# DecadeCounterViewer.net
KiCad netlist of a schematic drawn in EAGLE
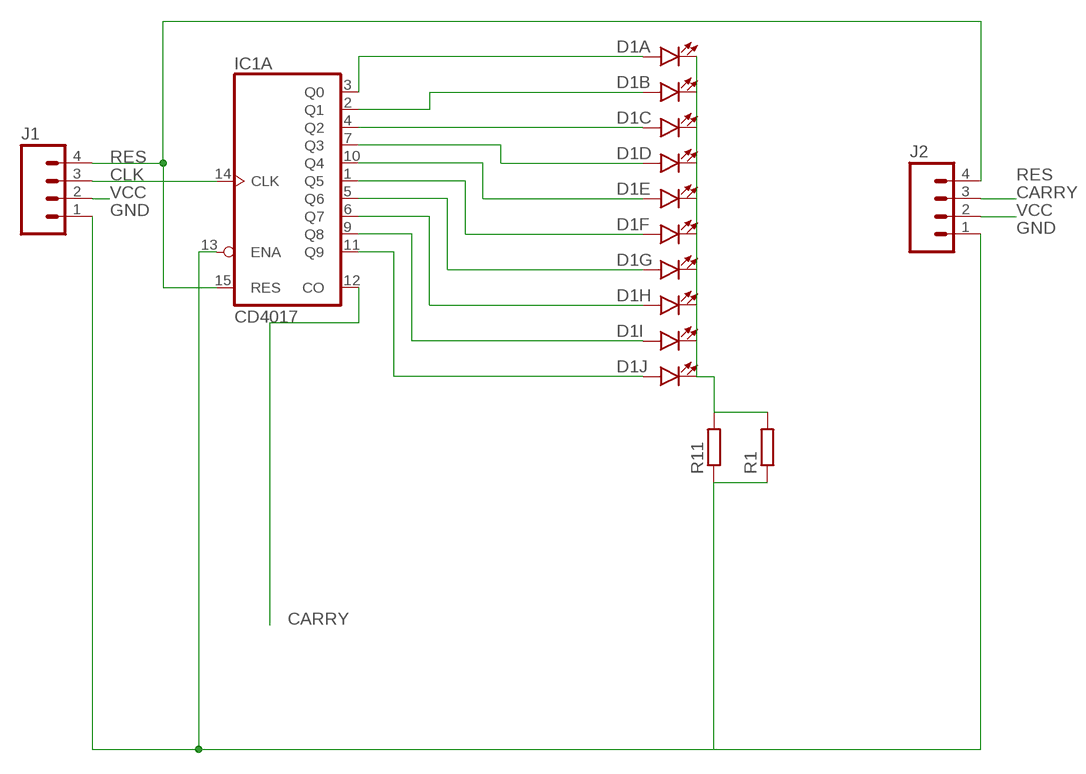
[diagram p0: schematic, sheet 1]

(export (version "E")
  (design (tool "Eeschema 10.0.6"))
  (components
    (comp (ref "D1")
      (value "LED_BARGRAPH_10")
      (footprint "eagle-import:LED_BARGAPH_10")
      (libsource (lib "eagle-import") (part "LED_BARGRAPH_10"))
    )
    (comp (ref "IC1")
      (value "CD4017")
      (footprint "eagle-import:DIL16")
      (libsource (lib "eagle-import") (part "CD4017"))
    )
    (comp (ref "J1")
      (value "M04LOCK")
      (footprint "eagle-import:1X04_LOCK")
      (libsource (lib "eagle-import") (part "M04LOCK"))
    )
    (comp (ref "J2")
      (value "M04LOCK")
      (footprint "eagle-import:1X04_LOCK")
      (libsource (lib "eagle-import") (part "M04LOCK"))
    )
    (comp (ref "R1")
      (value "R-EU_0204/7")
      (footprint "eagle-import:0204_7")
      (libsource (lib "eagle-import") (part "R-EU_0204/7"))
    )
    (comp (ref "R11")
      (value "R-EU_R1206")
      (footprint "eagle-import:R1206")
      (libsource (lib "eagle-import") (part "R-EU_R1206"))
    )
  )
  (nets
    (net (code "1") (name "/CARRY") (class "Default")
      (node (ref "IC1") (pin "12") (pinfunction "CO_12") (pintype "output"))
      (node (ref "J2") (pin "3") (pinfunction "3_3") (pintype "passive"))
    )
    (net (code "2") (name "/CLK") (class "Default")
      (node (ref "IC1") (pin "14") (pinfunction "CLK_14") (pintype "input"))
      (node (ref "J1") (pin "3") (pinfunction "3_3") (pintype "passive"))
    )
    (net (code "3") (name "/GND") (class "Default")
      (node (ref "IC1") (pin "13") (pinfunction "ENA_13") (pintype "input"))
      (node (ref "J1") (pin "1") (pinfunction "1_1") (pintype "passive"))
      (node (ref "J2") (pin "1") (pinfunction "1_1") (pintype "passive"))
      (node (ref "R1") (pin "1") (pinfunction "1_1") (pintype "passive"))
      (node (ref "R11") (pin "1") (pinfunction "1_1") (pintype "passive"))
    )
    (net (code "4") (name "/RES") (class "Default")
      (node (ref "IC1") (pin "15") (pinfunction "RES_15") (pintype "input"))
      (node (ref "J1") (pin "4") (pinfunction "4_4") (pintype "passive"))
      (node (ref "J2") (pin "4") (pinfunction "4_4") (pintype "passive"))
    )
    (net (code "5") (name "/VCC") (class "Default")
      (node (ref "J1") (pin "2") (pinfunction "2_2") (pintype "passive"))
      (node (ref "J2") (pin "2") (pinfunction "2_2") (pintype "passive"))
    )
    (net (code "6") (name "Net-(D1A-A)") (class "Default")
      (node (ref "D1") (pin "1") (pinfunction "A_1") (pintype "passive"))
      (node (ref "IC1") (pin "3") (pinfunction "Q0_3") (pintype "output"))
    )
    (net (code "7") (name "Net-(D1A-C)") (class "Default")
      (node (ref "D1") (pin "11") (pinfunction "C_11") (pintype "passive"))
      (node (ref "D1") (pin "12") (pinfunction "C_12") (pintype "passive"))
      (node (ref "D1") (pin "13") (pinfunction "C_13") (pintype "passive"))
      (node (ref "D1") (pin "14") (pinfunction "C_14") (pintype "passive"))
      (node (ref "D1") (pin "15") (pinfunction "C_15") (pintype "passive"))
      (node (ref "D1") (pin "16") (pinfunction "C_16") (pintype "passive"))
      (node (ref "D1") (pin "17") (pinfunction "C_17") (pintype "passive"))
      (node (ref "D1") (pin "18") (pinfunction "C_18") (pintype "passive"))
      (node (ref "D1") (pin "19") (pinfunction "C_19") (pintype "passive"))
      (node (ref "D1") (pin "20") (pinfunction "C_20") (pintype "passive"))
      (node (ref "R1") (pin "2") (pinfunction "2_2") (pintype "passive"))
      (node (ref "R11") (pin "2") (pinfunction "2_2") (pintype "passive"))
    )
    (net (code "8") (name "Net-(D1B-A)") (class "Default")
      (node (ref "D1") (pin "2") (pinfunction "A_2") (pintype "passive"))
      (node (ref "IC1") (pin "2") (pinfunction "Q1_2") (pintype "output"))
    )
    (net (code "9") (name "Net-(D1C-A)") (class "Default")
      (node (ref "D1") (pin "3") (pinfunction "A_3") (pintype "passive"))
      (node (ref "IC1") (pin "4") (pinfunction "Q2_4") (pintype "output"))
    )
    (net (code "10") (name "Net-(D1D-A)") (class "Default")
      (node (ref "D1") (pin "4") (pinfunction "A_4") (pintype "passive"))
      (node (ref "IC1") (pin "7") (pinfunction "Q3_7") (pintype "output"))
    )
    (net (code "11") (name "Net-(D1E-A)") (class "Default")
      (node (ref "D1") (pin "5") (pinfunction "A_5") (pintype "passive"))
      (node (ref "IC1") (pin "10") (pinfunction "Q4_10") (pintype "output"))
    )
    (net (code "12") (name "Net-(D1F-A)") (class "Default")
      (node (ref "D1") (pin "6") (pinfunction "A_6") (pintype "passive"))
      (node (ref "IC1") (pin "1") (pinfunction "Q5_1") (pintype "output"))
    )
    (net (code "13") (name "Net-(D1G-A)") (class "Default")
      (node (ref "D1") (pin "7") (pinfunction "A_7") (pintype "passive"))
      (node (ref "IC1") (pin "5") (pinfunction "Q6_5") (pintype "output"))
    )
    (net (code "14") (name "Net-(D1H-A)") (class "Default")
      (node (ref "D1") (pin "8") (pinfunction "A_8") (pintype "passive"))
      (node (ref "IC1") (pin "6") (pinfunction "Q7_6") (pintype "output"))
    )
    (net (code "15") (name "Net-(D1I-A)") (class "Default")
      (node (ref "D1") (pin "9") (pinfunction "A_9") (pintype "passive"))
      (node (ref "IC1") (pin "9") (pinfunction "Q8_9") (pintype "output"))
    )
    (net (code "16") (name "Net-(D1J-A)") (class "Default")
      (node (ref "D1") (pin "10") (pinfunction "A_10") (pintype "passive"))
      (node (ref "IC1") (pin "11") (pinfunction "Q9_11") (pintype "output"))
    )
  )
)
